# PreAmplifierVoltageA.net
KiCad netlist of a schematic drawn in Altium Designer
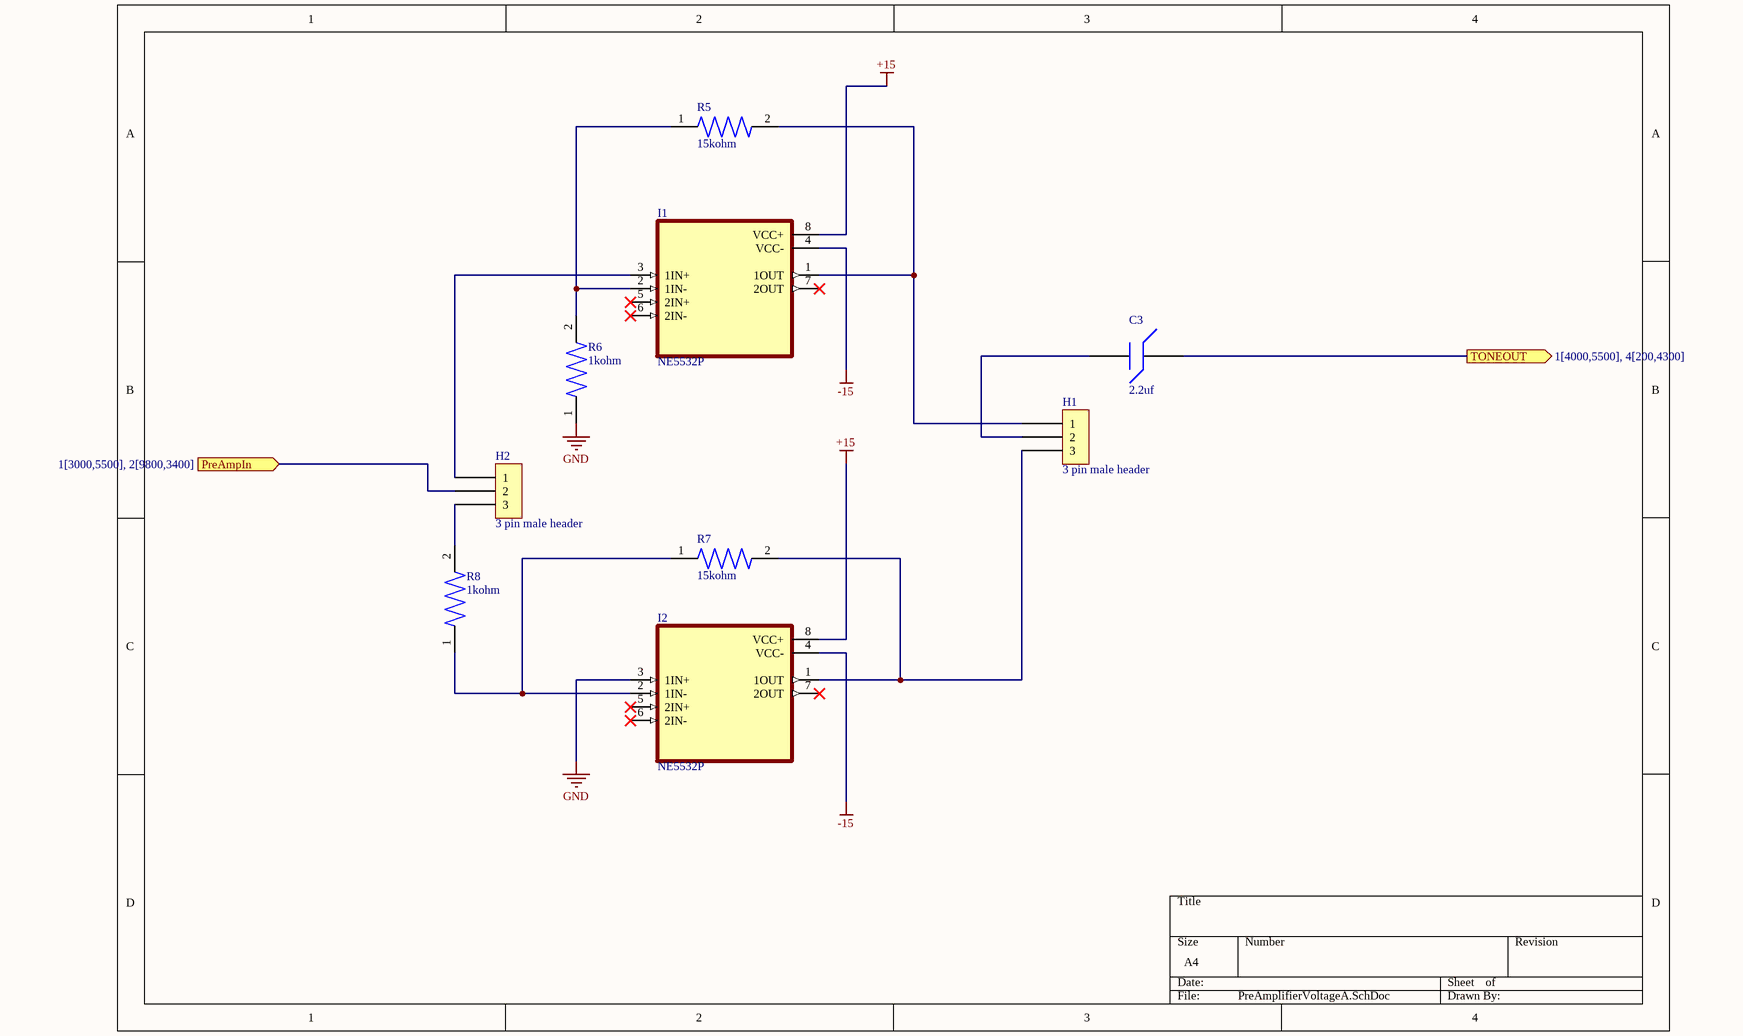
[diagram p0: PreAmplifierVoltageA.SchDoc]

(export (version "E")
  (design (tool "Eeschema 10.0.6"))
  (components
    (comp (ref "C3")
      (value "2.2uf")
      (footprint "Capasitor")
      (fields
        (field (name "MANUFACTURER") "Rubycon")
        (field (name "MANUFACTURER PART NUMBER") "400LLE2R2MEFC8X11.5")
      )
      (libsource (lib "AudioAmplifierBasic") (part "400LLE2R2MEFC8X11.5"))
    )
    (comp (ref "H1")
      (value "3 pin male header")
      (footprint "3 pin Male header")
      (fields (field (name "MANUFACTURER") "Harwin") (field (name "MANUFACTURER PART NUMBER") "M20-9990345"))
      (libsource (lib "AudioAmplifierBasic") (part "M20-9990345"))
    )
    (comp (ref "H2")
      (value "3 pin male header")
      (footprint "3 pin Male header")
      (fields (field (name "MANUFACTURER") "Harwin") (field (name "MANUFACTURER PART NUMBER") "M20-9990345"))
      (libsource (lib "AudioAmplifierBasic") (part "M20-9990345"))
    )
    (comp (ref "I1")
      (value "NE5532P")
      (footprint "NE5532P")
      (description "Operational Amplifier, 2 Func, 5000uV Offset-Max, BIPolar, PDIP8")
      (fields (field (name "MANUFACTURER") "Texas Instruments"))
      (libsource (lib "AudioAmplifierBasic") (part "NE5532P"))
    )
    (comp (ref "I2")
      (value "NE5532P")
      (footprint "NE5532P")
      (description "Operational Amplifier, 2 Func, 5000uV Offset-Max, BIPolar, PDIP8")
      (fields (field (name "MANUFACTURER") "Texas Instruments"))
      (libsource (lib "AudioAmplifierBasic") (part "NE5532P"))
    )
    (comp (ref "R5")
      (value "15kohm")
      (footprint "Resistor")
      (description "Fixed Resistor, Carbon Film, 0.5W, 15000ohm, 350V, 5% +/-Tol, -500,0ppm/Cel, Through Hole Mount")
      (fields
        (field (name "MANUFACTURER") "Stackpole Electronics")
        (field (name "MANUFACTURER PART NUMBER") "CFM12JT15K0")
      )
      (libsource (lib "AudioAmplifierBasic") (part "CFM12JT15K0"))
    )
    (comp (ref "R6")
      (value "1kohm")
      (footprint "Resistor")
      (description "Fixed Resistor, Carbon Film, 0.25W, 1000ohm, 350V, 5% +/-Tol, -400,0ppm/Cel, Through Hole Mount")
      (fields
        (field (name "MANUFACTURER") "Stackpole Electronics")
        (field (name "MANUFACTURER PART NUMBER") "CF14JT1K00")
      )
      (libsource (lib "AudioAmplifierBasic") (part "CF14JT1K00"))
    )
    (comp (ref "R7")
      (value "15kohm")
      (footprint "Resistor")
      (description "Fixed Resistor, Carbon Film, 0.5W, 15000ohm, 350V, 5% +/-Tol, -500,0ppm/Cel, Through Hole Mount")
      (fields
        (field (name "MANUFACTURER") "Stackpole Electronics")
        (field (name "MANUFACTURER PART NUMBER") "CFM12JT15K0")
      )
      (libsource (lib "AudioAmplifierBasic") (part "CFM12JT15K0"))
    )
    (comp (ref "R8")
      (value "1kohm")
      (footprint "Resistor")
      (description "Fixed Resistor, Carbon Film, 0.25W, 1000ohm, 350V, 5% +/-Tol, -400,0ppm/Cel, Through Hole Mount")
      (fields
        (field (name "MANUFACTURER") "Stackpole Electronics")
        (field (name "MANUFACTURER PART NUMBER") "CF14JT1K00")
      )
      (libsource (lib "AudioAmplifierBasic") (part "CF14JT1K00"))
    )
  )
  (nets
    (net (code "1") (name "+15") (class "Default")
      (node (ref "I1") (pin "8") (pinfunction "VCC+_8") (pintype "power_in"))
      (node (ref "I2") (pin "8") (pinfunction "VCC+_8") (pintype "power_in"))
    )
    (net (code "2") (name "-15") (class "Default")
      (node (ref "I1") (pin "4") (pinfunction "VCC-_4") (pintype "power_in"))
      (node (ref "I2") (pin "4") (pinfunction "VCC-_4") (pintype "power_in"))
    )
    (net (code "3") (name "/PreAmpIn") (class "Default")
      (node (ref "H2") (pin "2") (pinfunction "2_2") (pintype "passive"))
    )
    (net (code "4") (name "/TONEOUT") (class "Default")
      (node (ref "C3") (pin "2") (pinfunction "2_2") (pintype "passive"))
    )
    (net (code "5") (name "GND") (class "Default")
      (node (ref "I2") (pin "3") (pinfunction "1IN+_3") (pintype "input"))
      (node (ref "R6") (pin "1") (pinfunction "1_1") (pintype "passive"))
    )
    (net (code "6") (name "Net-(C3-Pad1)") (class "Default")
      (node (ref "C3") (pin "1") (pinfunction "1_1") (pintype "passive"))
      (node (ref "H1") (pin "2") (pinfunction "2_2") (pintype "passive"))
    )
    (net (code "7") (name "Net-(H2-Pad3)") (class "Default")
      (node (ref "H2") (pin "3") (pinfunction "3_3") (pintype "passive"))
      (node (ref "R8") (pin "2") (pinfunction "2_2") (pintype "passive"))
    )
    (net (code "8") (name "Net-(I1-1IN+)") (class "Default")
      (node (ref "H2") (pin "1") (pinfunction "1_1") (pintype "passive"))
      (node (ref "I1") (pin "3") (pinfunction "1IN+_3") (pintype "input"))
    )
    (net (code "9") (name "Net-(I1-1IN-)") (class "Default")
      (node (ref "I1") (pin "2") (pinfunction "1IN-_2") (pintype "input"))
      (node (ref "R5") (pin "1") (pinfunction "1_1") (pintype "passive"))
      (node (ref "R6") (pin "2") (pinfunction "2_2") (pintype "passive"))
    )
    (net (code "10") (name "Net-(I1-1OUT)") (class "Default")
      (node (ref "H1") (pin "1") (pinfunction "1_1") (pintype "passive"))
      (node (ref "I1") (pin "1") (pinfunction "1OUT_1") (pintype "output"))
      (node (ref "R5") (pin "2") (pinfunction "2_2") (pintype "passive"))
    )
    (net (code "11") (name "Net-(I2-1IN-)") (class "Default")
      (node (ref "I2") (pin "2") (pinfunction "1IN-_2") (pintype "input"))
      (node (ref "R7") (pin "1") (pinfunction "1_1") (pintype "passive"))
      (node (ref "R8") (pin "1") (pinfunction "1_1") (pintype "passive"))
    )
    (net (code "12") (name "Net-(I2-1OUT)") (class "Default")
      (node (ref "H1") (pin "3") (pinfunction "3_3") (pintype "passive"))
      (node (ref "I2") (pin "1") (pinfunction "1OUT_1") (pintype "output"))
      (node (ref "R7") (pin "2") (pinfunction "2_2") (pintype "passive"))
    )
    (net (code "13") (name "unconnected-(I1-2IN+-Pad5)") (class "Default")
      (node (ref "I1") (pin "5") (pinfunction "2IN+_5") (pintype "input+no_connect"))
    )
    (net (code "14") (name "unconnected-(I1-2IN--Pad6)") (class "Default")
      (node (ref "I1") (pin "6") (pinfunction "2IN-_6") (pintype "input+no_connect"))
    )
    (net (code "15") (name "unconnected-(I1-2OUT-Pad7)") (class "Default")
      (node (ref "I1") (pin "7") (pinfunction "2OUT_7") (pintype "output+no_connect"))
    )
    (net (code "16") (name "unconnected-(I2-2IN+-Pad5)") (class "Default")
      (node (ref "I2") (pin "5") (pinfunction "2IN+_5") (pintype "input+no_connect"))
    )
    (net (code "17") (name "unconnected-(I2-2IN--Pad6)") (class "Default")
      (node (ref "I2") (pin "6") (pinfunction "2IN-_6") (pintype "input+no_connect"))
    )
    (net (code "18") (name "unconnected-(I2-2OUT-Pad7)") (class "Default")
      (node (ref "I2") (pin "7") (pinfunction "2OUT_7") (pintype "output+no_connect"))
    )
  )
)
